# PCB-ENCODERSOLO_EM.net
KiCad netlist of a schematic drawn in EAGLE
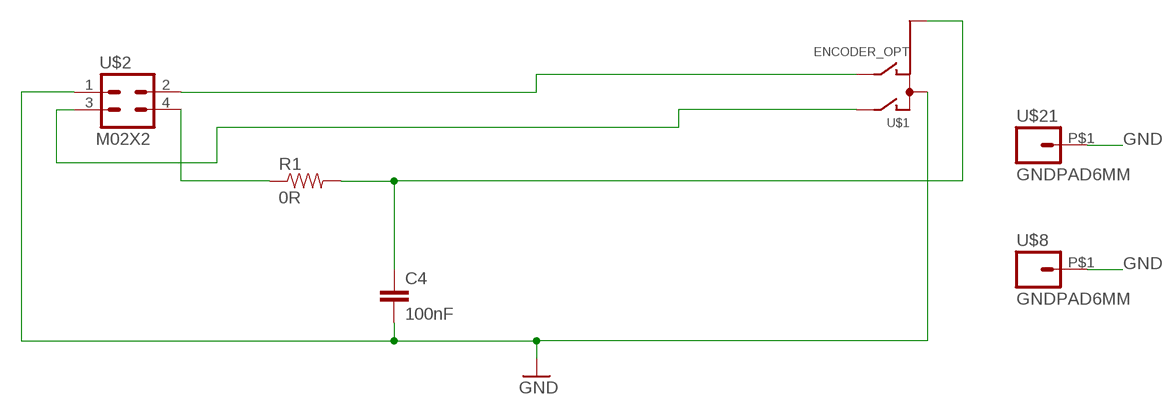
[diagram p0: schematic, sheet 1]

(export (version "E")
  (design (tool "Eeschema 10.0.6"))
  (components
    (comp (ref "C4")
      (value "100nF")
      (footprint "eagle-import:0603-CAP")
      (libsource (lib "eagle-import") (part "CAP0603-CAP"))
    )
    (comp (ref "R1")
      (value "0R")
      (footprint "eagle-import:0603-RES")
      (libsource (lib "eagle-import") (part "RESISTOR0603-RES"))
    )
    (comp (ref "U$1")
      (value "ENCODER_OPT")
      (footprint "eagle-import:ENCODER_EM14")
      (libsource (lib "eagle-import") (part "ENCODER_OPT"))
    )
    (comp (ref "U$2")
      (value "M02X2")
      (footprint "eagle-import:2X2")
      (libsource (lib "eagle-import") (part "M02X2"))
    )
    (comp (ref "U$8")
      (value "GNDPAD6MM")
      (footprint "eagle-import:3.2MMPAD6MM")
      (libsource (lib "eagle-import") (part "GNDPAD6MM"))
    )
    (comp (ref "U$21")
      (value "GNDPAD6MM")
      (footprint "eagle-import:3.2MMPAD6MM")
      (libsource (lib "eagle-import") (part "GNDPAD6MM"))
    )
  )
  (nets
    (net (code "1") (name "GND") (class "Default")
      (node (ref "C4") (pin "2") (pinfunction "2_2") (pintype "passive"))
      (node (ref "U$1") (pin "6") (pinfunction "GND_6") (pintype "power_in"))
      (node (ref "U$1") (pin "GND") (pinfunction "GND_GND") (pintype "power_in"))
      (node (ref "U$1") (pin "GND1") (pinfunction "GND_GND1") (pintype "power_in"))
      (node (ref "U$2") (pin "1") (pinfunction "1_1") (pintype "passive"))
      (node (ref "U$21") (pin "P$1") (pinfunction "1_P$1") (pintype "passive"))
      (node (ref "U$8") (pin "P$1") (pinfunction "1_P$1") (pintype "passive"))
    )
    (net (code "2") (name "Net-(R1-Pad1)") (class "Default")
      (node (ref "R1") (pin "1") (pinfunction "1_1") (pintype "passive"))
      (node (ref "U$2") (pin "4") (pinfunction "4_4") (pintype "passive"))
    )
    (net (code "3") (name "Net-(U$1-5V)") (class "Default")
      (node (ref "C4") (pin "1") (pinfunction "1_1") (pintype "passive"))
      (node (ref "R1") (pin "2") (pinfunction "2_2") (pintype "passive"))
      (node (ref "U$1") (pin "2") (pinfunction "5V_2") (pintype "power_in"))
    )
    (net (code "4") (name "Net-(U$1-A)") (class "Default")
      (node (ref "U$1") (pin "5") (pinfunction "A_5") (pintype "passive"))
      (node (ref "U$2") (pin "3") (pinfunction "3_3") (pintype "passive"))
    )
    (net (code "5") (name "Net-(U$1-B)") (class "Default")
      (node (ref "U$1") (pin "1") (pinfunction "B_1") (pintype "passive"))
      (node (ref "U$2") (pin "2") (pinfunction "2_2") (pintype "passive"))
    )
  )
)
